# fpga-serdes-outside.net
KiCad netlist of a schematic drawn in Altium Designer
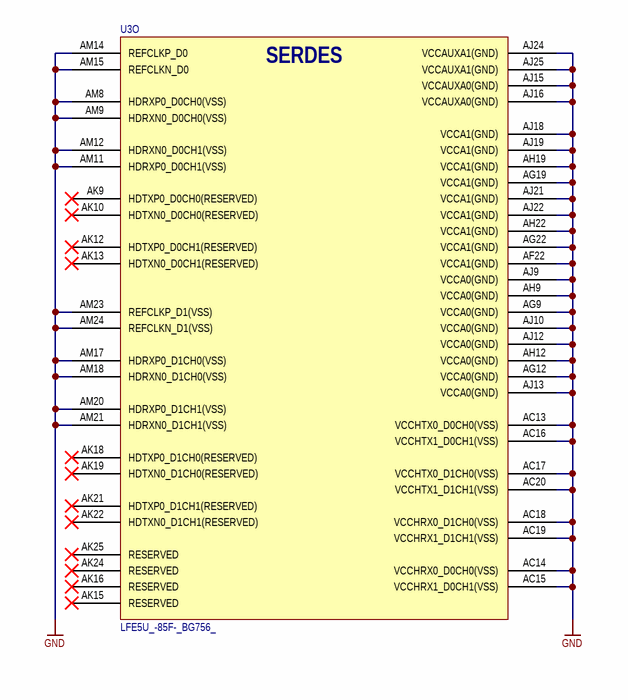
[diagram p0: fpga-serdes-outside.SchDoc]

(export (version "E")
  (design (tool "Eeschema 10.0.6"))
  (components
    (comp (ref "U3")
      (value "LFE5U_-85F-_BG756_")
      (footprint "lattice:caBGA756")
      (description "ECP5 FPGA, 85k LUT, 756-caBGA")
      (fields (field (name "MANUFACTURER") "Lattice Semiconductor"))
      (libsource (lib "lattice") (part "LFE5U_-85F-_BG756_"))
    )
  )
  (nets
    (net (code "1") (name "GND") (class "Default")
      (node (ref "U3") (pin "AC13") (pinfunction "VCCHTX0_D0CH0(VSS)_AC13") (pintype "power_in"))
      (node (ref "U3") (pin "AC14") (pinfunction "VCCHRX0_D0CH0(VSS)_AC14") (pintype "power_in"))
      (node (ref "U3") (pin "AC15") (pinfunction "VCCHRX1_D0CH1(VSS)_AC15") (pintype "power_in"))
      (node (ref "U3") (pin "AC16") (pinfunction "VCCHTX1_D0CH1(VSS)_AC16") (pintype "power_in"))
      (node (ref "U3") (pin "AC17") (pinfunction "VCCHTX0_D1CH0(VSS)_AC17") (pintype "power_in"))
      (node (ref "U3") (pin "AC18") (pinfunction "VCCHRX0_D1CH0(VSS)_AC18") (pintype "power_in"))
      (node (ref "U3") (pin "AC19") (pinfunction "VCCHRX1_D1CH1(VSS)_AC19") (pintype "power_in"))
      (node (ref "U3") (pin "AC20") (pinfunction "VCCHTX1_D1CH1(VSS)_AC20") (pintype "power_in"))
      (node (ref "U3") (pin "AF22") (pinfunction "VCCA1(GND)_AF22") (pintype "power_in"))
      (node (ref "U3") (pin "AG12") (pinfunction "VCCA0(GND)_AG12") (pintype "power_in"))
      (node (ref "U3") (pin "AG19") (pinfunction "VCCA1(GND)_AG19") (pintype "power_in"))
      (node (ref "U3") (pin "AG22") (pinfunction "VCCA1(GND)_AG22") (pintype "power_in"))
      (node (ref "U3") (pin "AG9") (pinfunction "VCCA0(GND)_AG9") (pintype "power_in"))
      (node (ref "U3") (pin "AH12") (pinfunction "VCCA0(GND)_AH12") (pintype "power_in"))
      (node (ref "U3") (pin "AH19") (pinfunction "VCCA1(GND)_AH19") (pintype "power_in"))
      (node (ref "U3") (pin "AH22") (pinfunction "VCCA1(GND)_AH22") (pintype "power_in"))
      (node (ref "U3") (pin "AH9") (pinfunction "VCCA0(GND)_AH9") (pintype "power_in"))
      (node (ref "U3") (pin "AJ10") (pinfunction "VCCA0(GND)_AJ10") (pintype "power_in"))
      (node (ref "U3") (pin "AJ12") (pinfunction "VCCA0(GND)_AJ12") (pintype "power_in"))
      (node (ref "U3") (pin "AJ13") (pinfunction "VCCA0(GND)_AJ13") (pintype "power_in"))
      (node (ref "U3") (pin "AJ15") (pinfunction "VCCAUXA0(GND)_AJ15") (pintype "power_in"))
      (node (ref "U3") (pin "AJ16") (pinfunction "VCCAUXA0(GND)_AJ16") (pintype "power_in"))
      (node (ref "U3") (pin "AJ18") (pinfunction "VCCA1(GND)_AJ18") (pintype "power_in"))
      (node (ref "U3") (pin "AJ19") (pinfunction "VCCA1(GND)_AJ19") (pintype "power_in"))
      (node (ref "U3") (pin "AJ21") (pinfunction "VCCA1(GND)_AJ21") (pintype "power_in"))
      (node (ref "U3") (pin "AJ22") (pinfunction "VCCA1(GND)_AJ22") (pintype "power_in"))
      (node (ref "U3") (pin "AJ24") (pinfunction "VCCAUXA1(GND)_AJ24") (pintype "power_in"))
      (node (ref "U3") (pin "AJ25") (pinfunction "VCCAUXA1(GND)_AJ25") (pintype "power_in"))
      (node (ref "U3") (pin "AJ9") (pinfunction "VCCA0(GND)_AJ9") (pintype "power_in"))
      (node (ref "U3") (pin "AM11") (pinfunction "HDRXP0_D0CH1(VSS)_AM11") (pintype "passive"))
      (node (ref "U3") (pin "AM12") (pinfunction "HDRXN0_D0CH1(VSS)_AM12") (pintype "passive"))
      (node (ref "U3") (pin "AM14") (pinfunction "REFCLKP_D0_AM14") (pintype "passive"))
      (node (ref "U3") (pin "AM15") (pinfunction "REFCLKN_D0_AM15") (pintype "passive"))
      (node (ref "U3") (pin "AM17") (pinfunction "HDRXP0_D1CH0(VSS)_AM17") (pintype "passive"))
      (node (ref "U3") (pin "AM18") (pinfunction "HDRXN0_D1CH0(VSS)_AM18") (pintype "passive"))
      (node (ref "U3") (pin "AM20") (pinfunction "HDRXP0_D1CH1(VSS)_AM20") (pintype "passive"))
      (node (ref "U3") (pin "AM21") (pinfunction "HDRXN0_D1CH1(VSS)_AM21") (pintype "passive"))
      (node (ref "U3") (pin "AM23") (pinfunction "REFCLKP_D1(VSS)_AM23") (pintype "passive"))
      (node (ref "U3") (pin "AM24") (pinfunction "REFCLKN_D1(VSS)_AM24") (pintype "passive"))
      (node (ref "U3") (pin "AM8") (pinfunction "HDRXP0_D0CH0(VSS)_AM8") (pintype "passive"))
      (node (ref "U3") (pin "AM9") (pinfunction "HDRXN0_D0CH0(VSS)_AM9") (pintype "passive"))
    )
    (net (code "2") (name "unconnected-(U3O-HDTXN0_D0CH0(RESERVED)-PadAK10)") (class "Default")
      (node (ref "U3") (pin "AK10") (pinfunction "HDTXN0_D0CH0(RESERVED)_AK10") (pintype "passive+no_connect"))
    )
    (net (code "3") (name "unconnected-(U3O-HDTXN0_D0CH1(RESERVED)-PadAK13)") (class "Default")
      (node (ref "U3") (pin "AK13") (pinfunction "HDTXN0_D0CH1(RESERVED)_AK13") (pintype "passive+no_connect"))
    )
    (net (code "4") (name "unconnected-(U3O-HDTXN0_D1CH0(RESERVED)-PadAK19)") (class "Default")
      (node (ref "U3") (pin "AK19") (pinfunction "HDTXN0_D1CH0(RESERVED)_AK19") (pintype "passive+no_connect"))
    )
    (net (code "5") (name "unconnected-(U3O-HDTXN0_D1CH1(RESERVED)-PadAK22)") (class "Default")
      (node (ref "U3") (pin "AK22") (pinfunction "HDTXN0_D1CH1(RESERVED)_AK22") (pintype "passive+no_connect"))
    )
    (net (code "6") (name "unconnected-(U3O-HDTXP0_D0CH0(RESERVED)-PadAK9)") (class "Default")
      (node (ref "U3") (pin "AK9") (pinfunction "HDTXP0_D0CH0(RESERVED)_AK9") (pintype "passive+no_connect"))
    )
    (net (code "7") (name "unconnected-(U3O-HDTXP0_D0CH1(RESERVED)-PadAK12)") (class "Default")
      (node (ref "U3") (pin "AK12") (pinfunction "HDTXP0_D0CH1(RESERVED)_AK12") (pintype "passive+no_connect"))
    )
    (net (code "8") (name "unconnected-(U3O-HDTXP0_D1CH0(RESERVED)-PadAK18)") (class "Default")
      (node (ref "U3") (pin "AK18") (pinfunction "HDTXP0_D1CH0(RESERVED)_AK18") (pintype "passive+no_connect"))
    )
    (net (code "9") (name "unconnected-(U3O-HDTXP0_D1CH1(RESERVED)-PadAK21)") (class "Default")
      (node (ref "U3") (pin "AK21") (pinfunction "HDTXP0_D1CH1(RESERVED)_AK21") (pintype "passive+no_connect"))
    )
    (net (code "10") (name "unconnected-(U3O-RESERVED-PadAK15)") (class "Default")
      (node (ref "U3") (pin "AK15") (pinfunction "RESERVED_AK15") (pintype "passive+no_connect"))
    )
    (net (code "11") (name "unconnected-(U3O-RESERVED-PadAK16)") (class "Default")
      (node (ref "U3") (pin "AK16") (pinfunction "RESERVED_AK16") (pintype "passive+no_connect"))
    )
    (net (code "12") (name "unconnected-(U3O-RESERVED-PadAK24)") (class "Default")
      (node (ref "U3") (pin "AK24") (pinfunction "RESERVED_AK24") (pintype "passive+no_connect"))
    )
    (net (code "13") (name "unconnected-(U3O-RESERVED-PadAK25)") (class "Default")
      (node (ref "U3") (pin "AK25") (pinfunction "RESERVED_AK25") (pintype "passive+no_connect"))
    )
  )
)
